# design.net
KiCad netlist of a schematic drawn in EasyEDA Pro
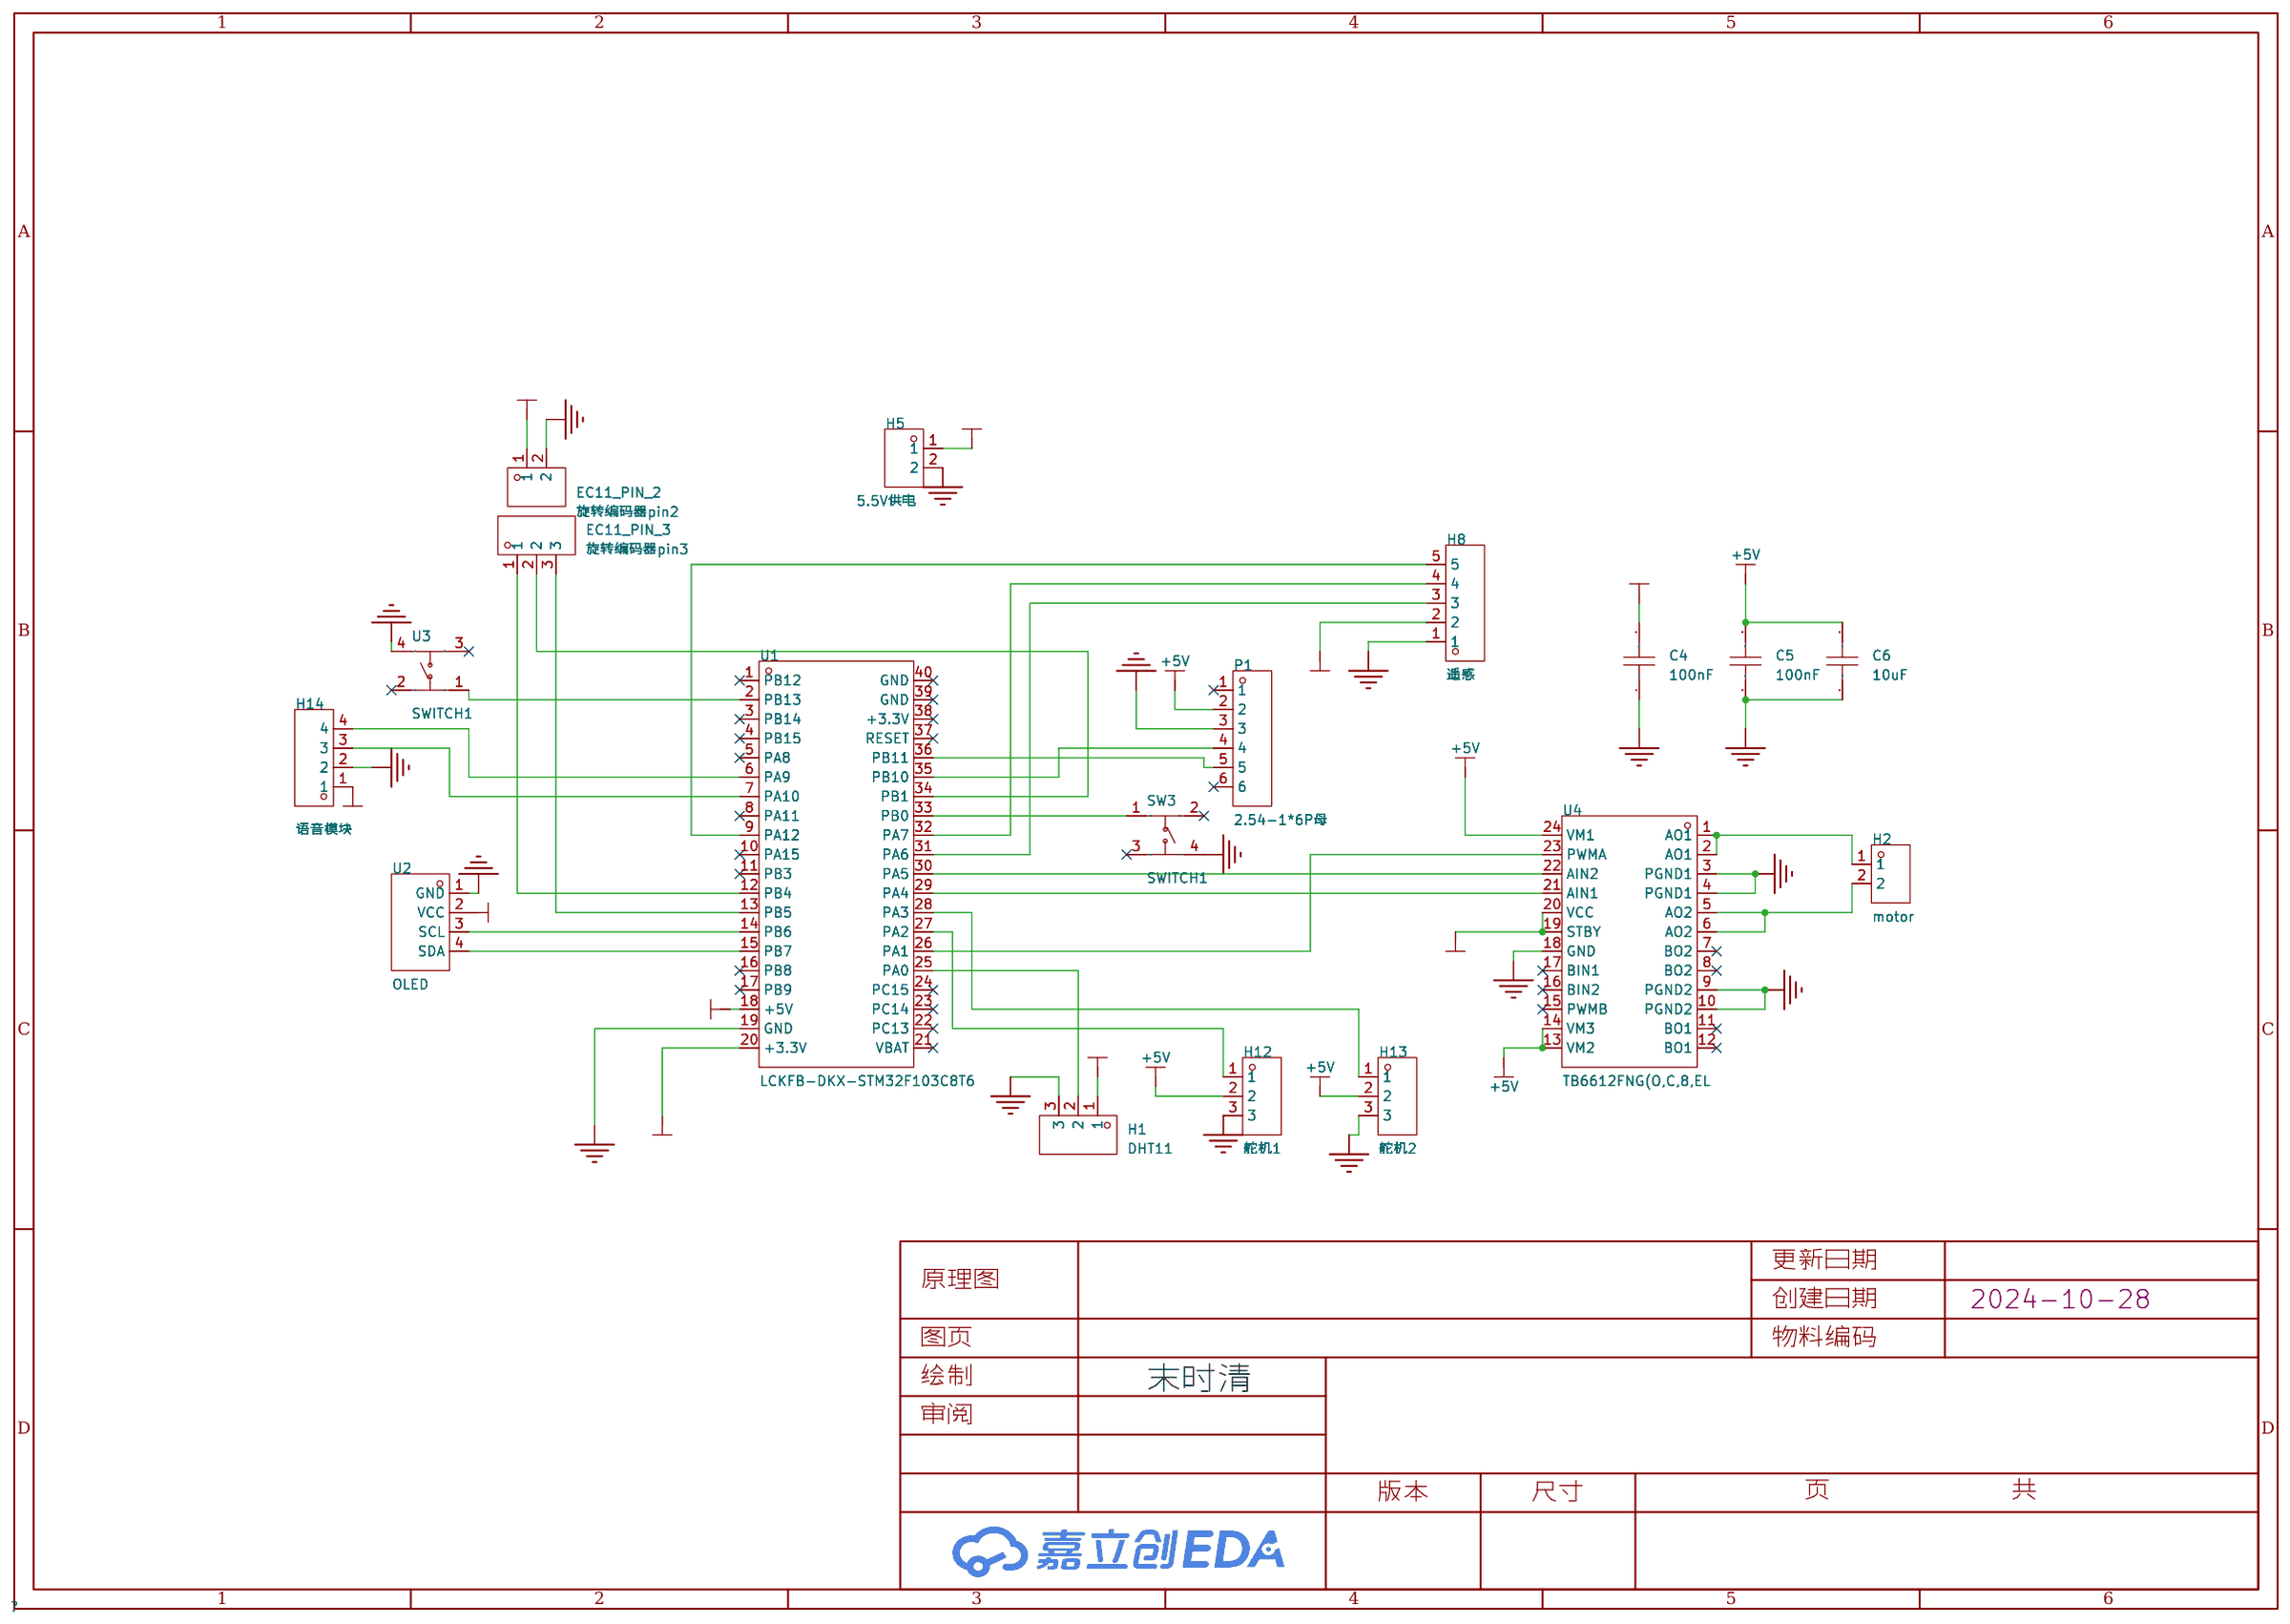
[diagram p0: schematic sheet]

(export (version "E")
  (design (tool "Eeschema 10.0.6"))
  (components
    (comp (ref "C4")
      (value "100nF")
      (footprint "easyedapro:C0805")
      (libsource (lib "easyedapro") (part "CapAcitance"))
    )
    (comp (ref "C5")
      (value "100nF")
      (footprint "easyedapro:C0805")
      (libsource (lib "easyedapro") (part "CapAcitance"))
    )
    (comp (ref "C6")
      (value "100nF")
      (footprint "easyedapro:C0805")
      (libsource (lib "easyedapro") (part "CapAcitance"))
    )
    (comp (ref "EC11_PIN_2")
      (value "旋转编码器pin2")
      (footprint "easyedapro:HDR-TH_2P-P2.54-V-M")
      (fields (field (name "Manufacturer") "XFCN(兴飞)"))
      (libsource (lib "easyedapro") (part "PZ254V-11-02P"))
    )
    (comp (ref "EC11_PIN_3")
      (value "旋转编码器pin3")
      (footprint "easyedapro:HDR-TH_3P-P2.54-V-M")
      (fields (field (name "Manufacturer") "XFCN(兴飞)"))
      (libsource (lib "easyedapro") (part "PZ254V-11-03P_C2937625"))
    )
    (comp (ref "H1")
      (value "DHT11")
      (footprint "easyedapro:HDR-TH_3P-P2.54-V-F")
      (description "插孔结构:1x3P;间距:2.54mm;行距:-;安装类型:直插;排数:单排;总孔位数:3P;塑高:-;触头材质:黄铜;触头镀层:-;")
      (fields (field (name "Manufacturer") "XFCN(兴飞)"))
      (libsource (lib "easyedapro") (part "PM254V-11-03-H85"))
    )
    (comp (ref "H2")
      (value "motor")
      (footprint "easyedapro:HDR-TH_2P-P2.54-V-M")
      (fields (field (name "Manufacturer") "XFCN(兴飞)"))
      (libsource (lib "easyedapro") (part "PZ254V-11-02P"))
    )
    (comp (ref "H5")
      (value "5.5V供电")
      (footprint "easyedapro:HDR-TH_2P-P2.54-V-M")
      (fields (field (name "Manufacturer") "XFCN(兴飞)"))
      (libsource (lib "easyedapro") (part "PZ254V-11-02P"))
    )
    (comp (ref "H8")
      (value "遥感")
      (footprint "easyedapro:HDR-TH_5P-P2.54-V-M")
      (fields (field (name "Manufacturer") "XFCN(兴飞)"))
      (libsource (lib "easyedapro") (part "PZ254V-11-05P"))
    )
    (comp (ref "H12")
      (value "舵机1")
      (footprint "easyedapro:HDR-TH_3P-P2.54-V-M")
      (fields (field (name "Manufacturer") "XFCN(兴飞)"))
      (libsource (lib "easyedapro") (part "PZ254V-11-03P_C2937625"))
    )
    (comp (ref "H13")
      (value "舵机2")
      (footprint "easyedapro:HDR-TH_3P-P2.54-V-M")
      (fields (field (name "Manufacturer") "XFCN(兴飞)"))
      (libsource (lib "easyedapro") (part "PZ254V-11-03P_C2937625"))
    )
    (comp (ref "H14")
      (value "语音模块")
      (footprint "easyedapro:HDR-TH_4P-P2.54-V-M")
      (fields (field (name "Manufacturer") "XFCN(兴飞)"))
      (libsource (lib "easyedapro") (part "PZ254V-11-04P_C2691448"))
    )
    (comp (ref "P1")
      (value "2.54-1*6P母")
      (footprint "easyedapro:HDR-TH_6P-P2.54-V-F")
      (description "插孔结构:1x6P;间距:2.54mm;行距:-;安装类型:直插;排数:单排;总孔位数:6P;塑高:-;触头材质:-;触头镀层:-;")
      (fields (field (name "Manufacturer") "BOOMELE(博穆精密)"))
      (libsource (lib "easyedapro") (part "Header-Female-2.54_1x6"))
    )
    (comp (ref "SW3")
      (value "SWITCH1")
      (footprint "easyedapro:SW-SMD_4P-L6.0-W6.0-P4.50-LS9.0-2")
      (description "电路结构:单刀单掷;按钮形状:圆形按钮;安装方式:立贴;开关长度:6mm;开关宽度:6mm;开关高度:5mm;带支架:不带;触点电流:50mA;额定电压(DC):12V;机械寿命:8万次;")
      (fields (field (name "Manufacturer") "kinghelm(金航标)"))
      (libsource (lib "easyedapro") (part "KH-6X6X5H-STM"))
    )
    (comp (ref "U1")
      (value "LCKFB-DKX-STM32F103C8T6")
      (footprint "easyedapro:CONN-TH_L53.3-W22.9_STM32F103C8T6-CARD")
      (fields (field (name "Manufacturer") "立创开发板"))
      (libsource (lib "easyedapro") (part "LCKFB-DKX-STM32F103C8T6"))
    )
    (comp (ref "U2")
      (value "OLED")
      (footprint "easyedapro:OLED-TH_L27.8-W27.2-P2.54_C9900033791")
      (description "主控芯片:SSD1315;接口类型:I2C;尺寸(inch):0.96;像素分辨率:128x64;")
      (fields (field (name "Manufacturer") "HS(汉昇)"))
      (libsource (lib "easyedapro") (part "HS96L03W2C03"))
    )
    (comp (ref "U3")
      (value "SWITCH1")
      (footprint "easyedapro:SW-SMD_4P-L6.0-W6.0-P4.50-LS9.0-2")
      (description "电路结构:单刀单掷;按钮形状:圆形按钮;安装方式:立贴;开关长度:6mm;开关宽度:6mm;开关高度:5mm;带支架:不带;触点电流:50mA;额定电压(DC):12V;机械寿命:8万次;")
      (fields (field (name "Manufacturer") "kinghelm(金航标)"))
      (libsource (lib "easyedapro") (part "KH-6X6X5H-STM"))
    )
    (comp (ref "U4")
      (value "TB6612FNG(O,C,8,EL")
      (footprint "easyedapro:SSOP-24_L8.4-W5.8-P0.65-LS7.8-BL")
      (description "双直流电机驱动器集成电路")
      (fields (field (name "Manufacturer") "TOSHIBA(东芝)"))
      (libsource (lib "easyedapro") (part "TB6612FNG(O,C,8,EL"))
    )
  )
  (nets
    (net (code "1") (name "+3.3V") (class "Default")
      (node (ref "C4") (pin "2") (pinfunction "2_2") (pintype "input"))
      (node (ref "EC11_PIN_2") (pin "1") (pinfunction "1_1") (pintype "unspecified"))
      (node (ref "H1") (pin "1") (pinfunction "1_1") (pintype "unspecified"))
      (node (ref "U1") (pin "20") (pinfunction "+3.3V_20") (pintype "unspecified"))
      (node (ref "U2") (pin "2") (pinfunction "VCC_2") (pintype "unspecified"))
      (node (ref "U4") (pin "19") (pinfunction "STBY_19") (pintype "unspecified"))
      (node (ref "U4") (pin "20") (pinfunction "VCC_20") (pintype "unspecified"))
    )
    (net (code "2") (name "+5V") (class "Default")
      (node (ref "C5") (pin "2") (pinfunction "2_2") (pintype "input"))
      (node (ref "C6") (pin "2") (pinfunction "2_2") (pintype "input"))
      (node (ref "H12") (pin "2") (pinfunction "2_2") (pintype "unspecified"))
      (node (ref "H13") (pin "2") (pinfunction "2_2") (pintype "unspecified"))
      (node (ref "H14") (pin "1") (pinfunction "1_1") (pintype "unspecified"))
      (node (ref "H5") (pin "1") (pinfunction "1_1") (pintype "unspecified"))
      (node (ref "H8") (pin "2") (pinfunction "2_2") (pintype "unspecified"))
      (node (ref "P1") (pin "2") (pinfunction "2_2") (pintype "unspecified"))
      (node (ref "U1") (pin "18") (pinfunction "+5V_18") (pintype "unspecified"))
      (node (ref "U4") (pin "13") (pinfunction "VM2_13") (pintype "unspecified"))
      (node (ref "U4") (pin "14") (pinfunction "VM3_14") (pintype "unspecified"))
      (node (ref "U4") (pin "24") (pinfunction "VM1_24") (pintype "unspecified"))
    )
    (net (code "3") (name "GND") (class "Default")
      (node (ref "C4") (pin "1") (pinfunction "1_1") (pintype "input"))
      (node (ref "C5") (pin "1") (pinfunction "1_1") (pintype "input"))
      (node (ref "C6") (pin "1") (pinfunction "1_1") (pintype "input"))
      (node (ref "EC11_PIN_2") (pin "2") (pinfunction "2_2") (pintype "unspecified"))
      (node (ref "H1") (pin "3") (pinfunction "3_3") (pintype "unspecified"))
      (node (ref "H12") (pin "3") (pinfunction "3_3") (pintype "unspecified"))
      (node (ref "H13") (pin "3") (pinfunction "3_3") (pintype "unspecified"))
      (node (ref "H14") (pin "2") (pinfunction "2_2") (pintype "unspecified"))
      (node (ref "H5") (pin "2") (pinfunction "2_2") (pintype "unspecified"))
      (node (ref "H8") (pin "1") (pinfunction "1_1") (pintype "unspecified"))
      (node (ref "P1") (pin "3") (pinfunction "3_3") (pintype "unspecified"))
      (node (ref "SW3") (pin "4") (pinfunction "4_4") (pintype "unspecified"))
      (node (ref "U1") (pin "19") (pinfunction "GND_19") (pintype "unspecified"))
      (node (ref "U2") (pin "1") (pinfunction "GND_1") (pintype "unspecified"))
      (node (ref "U3") (pin "4") (pinfunction "4_4") (pintype "unspecified"))
      (node (ref "U4") (pin "10") (pinfunction "PGND2_10") (pintype "unspecified"))
      (node (ref "U4") (pin "18") (pinfunction "GND_18") (pintype "unspecified"))
      (node (ref "U4") (pin "3") (pinfunction "PGND1_3") (pintype "unspecified"))
      (node (ref "U4") (pin "4") (pinfunction "PGND1_4") (pintype "unspecified"))
      (node (ref "U4") (pin "9") (pinfunction "PGND2_9") (pintype "unspecified"))
    )
    (net (code "4") (name "Net-(H2-Pad1)") (class "Default")
      (node (ref "H2") (pin "1") (pinfunction "1_1") (pintype "unspecified"))
      (node (ref "U4") (pin "1") (pinfunction "AO1_1") (pintype "unspecified"))
      (node (ref "U4") (pin "2") (pinfunction "AO1_2") (pintype "unspecified"))
    )
    (net (code "5") (name "Net-(H2-Pad2)") (class "Default")
      (node (ref "H2") (pin "2") (pinfunction "2_2") (pintype "unspecified"))
      (node (ref "U4") (pin "5") (pinfunction "AO2_5") (pintype "unspecified"))
      (node (ref "U4") (pin "6") (pinfunction "AO2_6") (pintype "unspecified"))
    )
    (net (code "6") (name "Net-(U1-PA0)") (class "Default")
      (node (ref "H1") (pin "2") (pinfunction "2_2") (pintype "unspecified"))
      (node (ref "U1") (pin "25") (pinfunction "PA0_25") (pintype "unspecified"))
    )
    (net (code "7") (name "Net-(U1-PA1)") (class "Default")
      (node (ref "U1") (pin "26") (pinfunction "PA1_26") (pintype "unspecified"))
      (node (ref "U4") (pin "23") (pinfunction "PWMA_23") (pintype "unspecified"))
    )
    (net (code "8") (name "Net-(U1-PA2)") (class "Default")
      (node (ref "H12") (pin "1") (pinfunction "1_1") (pintype "unspecified"))
      (node (ref "U1") (pin "27") (pinfunction "PA2_27") (pintype "unspecified"))
    )
    (net (code "9") (name "Net-(U1-PA3)") (class "Default")
      (node (ref "H13") (pin "1") (pinfunction "1_1") (pintype "unspecified"))
      (node (ref "U1") (pin "28") (pinfunction "PA3_28") (pintype "unspecified"))
    )
    (net (code "10") (name "Net-(U1-PA4)") (class "Default")
      (node (ref "U1") (pin "29") (pinfunction "PA4_29") (pintype "unspecified"))
      (node (ref "U4") (pin "21") (pinfunction "AIN1_21") (pintype "unspecified"))
    )
    (net (code "11") (name "Net-(U1-PA5)") (class "Default")
      (node (ref "U1") (pin "30") (pinfunction "PA5_30") (pintype "unspecified"))
      (node (ref "U4") (pin "22") (pinfunction "AIN2_22") (pintype "unspecified"))
    )
    (net (code "12") (name "Net-(U1-PA6)") (class "Default")
      (node (ref "H8") (pin "3") (pinfunction "3_3") (pintype "unspecified"))
      (node (ref "U1") (pin "31") (pinfunction "PA6_31") (pintype "unspecified"))
    )
    (net (code "13") (name "Net-(U1-PA7)") (class "Default")
      (node (ref "H8") (pin "4") (pinfunction "4_4") (pintype "unspecified"))
      (node (ref "U1") (pin "32") (pinfunction "PA7_32") (pintype "unspecified"))
    )
    (net (code "14") (name "Net-(U1-PA9)") (class "Default")
      (node (ref "H14") (pin "4") (pinfunction "4_4") (pintype "unspecified"))
      (node (ref "U1") (pin "6") (pinfunction "PA9_6") (pintype "unspecified"))
    )
    (net (code "15") (name "Net-(U1-PA10)") (class "Default")
      (node (ref "H14") (pin "3") (pinfunction "3_3") (pintype "unspecified"))
      (node (ref "U1") (pin "7") (pinfunction "PA10_7") (pintype "unspecified"))
    )
    (net (code "16") (name "Net-(U1-PA12)") (class "Default")
      (node (ref "H8") (pin "5") (pinfunction "5_5") (pintype "unspecified"))
      (node (ref "U1") (pin "9") (pinfunction "PA12_9") (pintype "unspecified"))
    )
    (net (code "17") (name "Net-(U1-PB0)") (class "Default")
      (node (ref "SW3") (pin "1") (pinfunction "1_1") (pintype "unspecified"))
      (node (ref "U1") (pin "33") (pinfunction "PB0_33") (pintype "unspecified"))
    )
    (net (code "18") (name "Net-(U1-PB1)") (class "Default")
      (node (ref "EC11_PIN_3") (pin "2") (pinfunction "2_2") (pintype "unspecified"))
      (node (ref "U1") (pin "34") (pinfunction "PB1_34") (pintype "unspecified"))
    )
    (net (code "19") (name "Net-(U1-PB4)") (class "Default")
      (node (ref "EC11_PIN_3") (pin "1") (pinfunction "1_1") (pintype "unspecified"))
      (node (ref "U1") (pin "12") (pinfunction "PB4_12") (pintype "unspecified"))
    )
    (net (code "20") (name "Net-(U1-PB5)") (class "Default")
      (node (ref "EC11_PIN_3") (pin "3") (pinfunction "3_3") (pintype "unspecified"))
      (node (ref "U1") (pin "13") (pinfunction "PB5_13") (pintype "unspecified"))
    )
    (net (code "21") (name "Net-(U1-PB6)") (class "Default")
      (node (ref "U1") (pin "14") (pinfunction "PB6_14") (pintype "unspecified"))
      (node (ref "U2") (pin "3") (pinfunction "SCL_3") (pintype "unspecified"))
    )
    (net (code "22") (name "Net-(U1-PB7)") (class "Default")
      (node (ref "U1") (pin "15") (pinfunction "PB7_15") (pintype "unspecified"))
      (node (ref "U2") (pin "4") (pinfunction "SDA_4") (pintype "unspecified"))
    )
    (net (code "23") (name "Net-(U1-PB10)") (class "Default")
      (node (ref "P1") (pin "4") (pinfunction "4_4") (pintype "unspecified"))
      (node (ref "U1") (pin "35") (pinfunction "PB10_35") (pintype "unspecified"))
    )
    (net (code "24") (name "Net-(U1-PB11)") (class "Default")
      (node (ref "P1") (pin "5") (pinfunction "5_5") (pintype "unspecified"))
      (node (ref "U1") (pin "36") (pinfunction "PB11_36") (pintype "unspecified"))
    )
    (net (code "25") (name "Net-(U1-PB13)") (class "Default")
      (node (ref "U1") (pin "2") (pinfunction "PB13_2") (pintype "unspecified"))
      (node (ref "U3") (pin "1") (pinfunction "1_1") (pintype "unspecified"))
    )
    (net (code "26") (name "unconnected-(P1-Pad1)") (class "Default")
      (node (ref "P1") (pin "1") (pinfunction "1_1") (pintype "unspecified+no_connect"))
    )
    (net (code "27") (name "unconnected-(P1-Pad6)") (class "Default")
      (node (ref "P1") (pin "6") (pinfunction "6_6") (pintype "unspecified+no_connect"))
    )
    (net (code "28") (name "unconnected-(SW3-Pad2)") (class "Default")
      (node (ref "SW3") (pin "2") (pinfunction "2_2") (pintype "unspecified+no_connect"))
    )
    (net (code "29") (name "unconnected-(SW3-Pad3)") (class "Default")
      (node (ref "SW3") (pin "3") (pinfunction "3_3") (pintype "unspecified+no_connect"))
    )
    (net (code "30") (name "unconnected-(U1-+3.3V-Pad38)") (class "Default")
      (node (ref "U1") (pin "38") (pinfunction "+3.3V_38") (pintype "unspecified+no_connect"))
    )
    (net (code "31") (name "unconnected-(U1-GND-Pad39)") (class "Default")
      (node (ref "U1") (pin "39") (pinfunction "GND_39") (pintype "unspecified+no_connect"))
    )
    (net (code "32") (name "unconnected-(U1-GND-Pad40)") (class "Default")
      (node (ref "U1") (pin "40") (pinfunction "GND_40") (pintype "unspecified+no_connect"))
    )
    (net (code "33") (name "unconnected-(U1-PA8-Pad5)") (class "Default")
      (node (ref "U1") (pin "5") (pinfunction "PA8_5") (pintype "unspecified+no_connect"))
    )
    (net (code "34") (name "unconnected-(U1-PA11-Pad8)") (class "Default")
      (node (ref "U1") (pin "8") (pinfunction "PA11_8") (pintype "unspecified+no_connect"))
    )
    (net (code "35") (name "unconnected-(U1-PA15-Pad10)") (class "Default")
      (node (ref "U1") (pin "10") (pinfunction "PA15_10") (pintype "unspecified+no_connect"))
    )
    (net (code "36") (name "unconnected-(U1-PB3-Pad11)") (class "Default")
      (node (ref "U1") (pin "11") (pinfunction "PB3_11") (pintype "unspecified+no_connect"))
    )
    (net (code "37") (name "unconnected-(U1-PB8-Pad16)") (class "Default")
      (node (ref "U1") (pin "16") (pinfunction "PB8_16") (pintype "unspecified+no_connect"))
    )
    (net (code "38") (name "unconnected-(U1-PB9-Pad17)") (class "Default")
      (node (ref "U1") (pin "17") (pinfunction "PB9_17") (pintype "unspecified+no_connect"))
    )
    (net (code "39") (name "unconnected-(U1-PB12-Pad1)") (class "Default")
      (node (ref "U1") (pin "1") (pinfunction "PB12_1") (pintype "unspecified+no_connect"))
    )
    (net (code "40") (name "unconnected-(U1-PB14-Pad3)") (class "Default")
      (node (ref "U1") (pin "3") (pinfunction "PB14_3") (pintype "unspecified+no_connect"))
    )
    (net (code "41") (name "unconnected-(U1-PB15-Pad4)") (class "Default")
      (node (ref "U1") (pin "4") (pinfunction "PB15_4") (pintype "unspecified+no_connect"))
    )
    (net (code "42") (name "unconnected-(U1-PC13-Pad22)") (class "Default")
      (node (ref "U1") (pin "22") (pinfunction "PC13_22") (pintype "unspecified+no_connect"))
    )
    (net (code "43") (name "unconnected-(U1-PC14-Pad23)") (class "Default")
      (node (ref "U1") (pin "23") (pinfunction "PC14_23") (pintype "unspecified+no_connect"))
    )
    (net (code "44") (name "unconnected-(U1-PC15-Pad24)") (class "Default")
      (node (ref "U1") (pin "24") (pinfunction "PC15_24") (pintype "unspecified+no_connect"))
    )
    (net (code "45") (name "unconnected-(U1-RESET-Pad37)") (class "Default")
      (node (ref "U1") (pin "37") (pinfunction "RESET_37") (pintype "unspecified+no_connect"))
    )
    (net (code "46") (name "unconnected-(U1-VBAT-Pad21)") (class "Default")
      (node (ref "U1") (pin "21") (pinfunction "VBAT_21") (pintype "unspecified+no_connect"))
    )
    (net (code "47") (name "unconnected-(U3-Pad2)") (class "Default")
      (node (ref "U3") (pin "2") (pinfunction "2_2") (pintype "unspecified+no_connect"))
    )
    (net (code "48") (name "unconnected-(U3-Pad3)") (class "Default")
      (node (ref "U3") (pin "3") (pinfunction "3_3") (pintype "unspecified+no_connect"))
    )
    (net (code "49") (name "unconnected-(U4-BIN1-Pad17)") (class "Default")
      (node (ref "U4") (pin "17") (pinfunction "BIN1_17") (pintype "unspecified+no_connect"))
    )
    (net (code "50") (name "unconnected-(U4-BIN2-Pad16)") (class "Default")
      (node (ref "U4") (pin "16") (pinfunction "BIN2_16") (pintype "unspecified+no_connect"))
    )
    (net (code "51") (name "unconnected-(U4-BO1-Pad11)") (class "Default")
      (node (ref "U4") (pin "11") (pinfunction "BO1_11") (pintype "unspecified+no_connect"))
    )
    (net (code "52") (name "unconnected-(U4-BO1-Pad12)") (class "Default")
      (node (ref "U4") (pin "12") (pinfunction "BO1_12") (pintype "unspecified+no_connect"))
    )
    (net (code "53") (name "unconnected-(U4-BO2-Pad7)") (class "Default")
      (node (ref "U4") (pin "7") (pinfunction "BO2_7") (pintype "unspecified+no_connect"))
    )
    (net (code "54") (name "unconnected-(U4-BO2-Pad8)") (class "Default")
      (node (ref "U4") (pin "8") (pinfunction "BO2_8") (pintype "unspecified+no_connect"))
    )
    (net (code "55") (name "unconnected-(U4-PWMB-Pad15)") (class "Default")
      (node (ref "U4") (pin "15") (pinfunction "PWMB_15") (pintype "unspecified+no_connect"))
    )
  )
)
